# V1.net
KiCad netlist of a schematic drawn in EasyEDA Pro
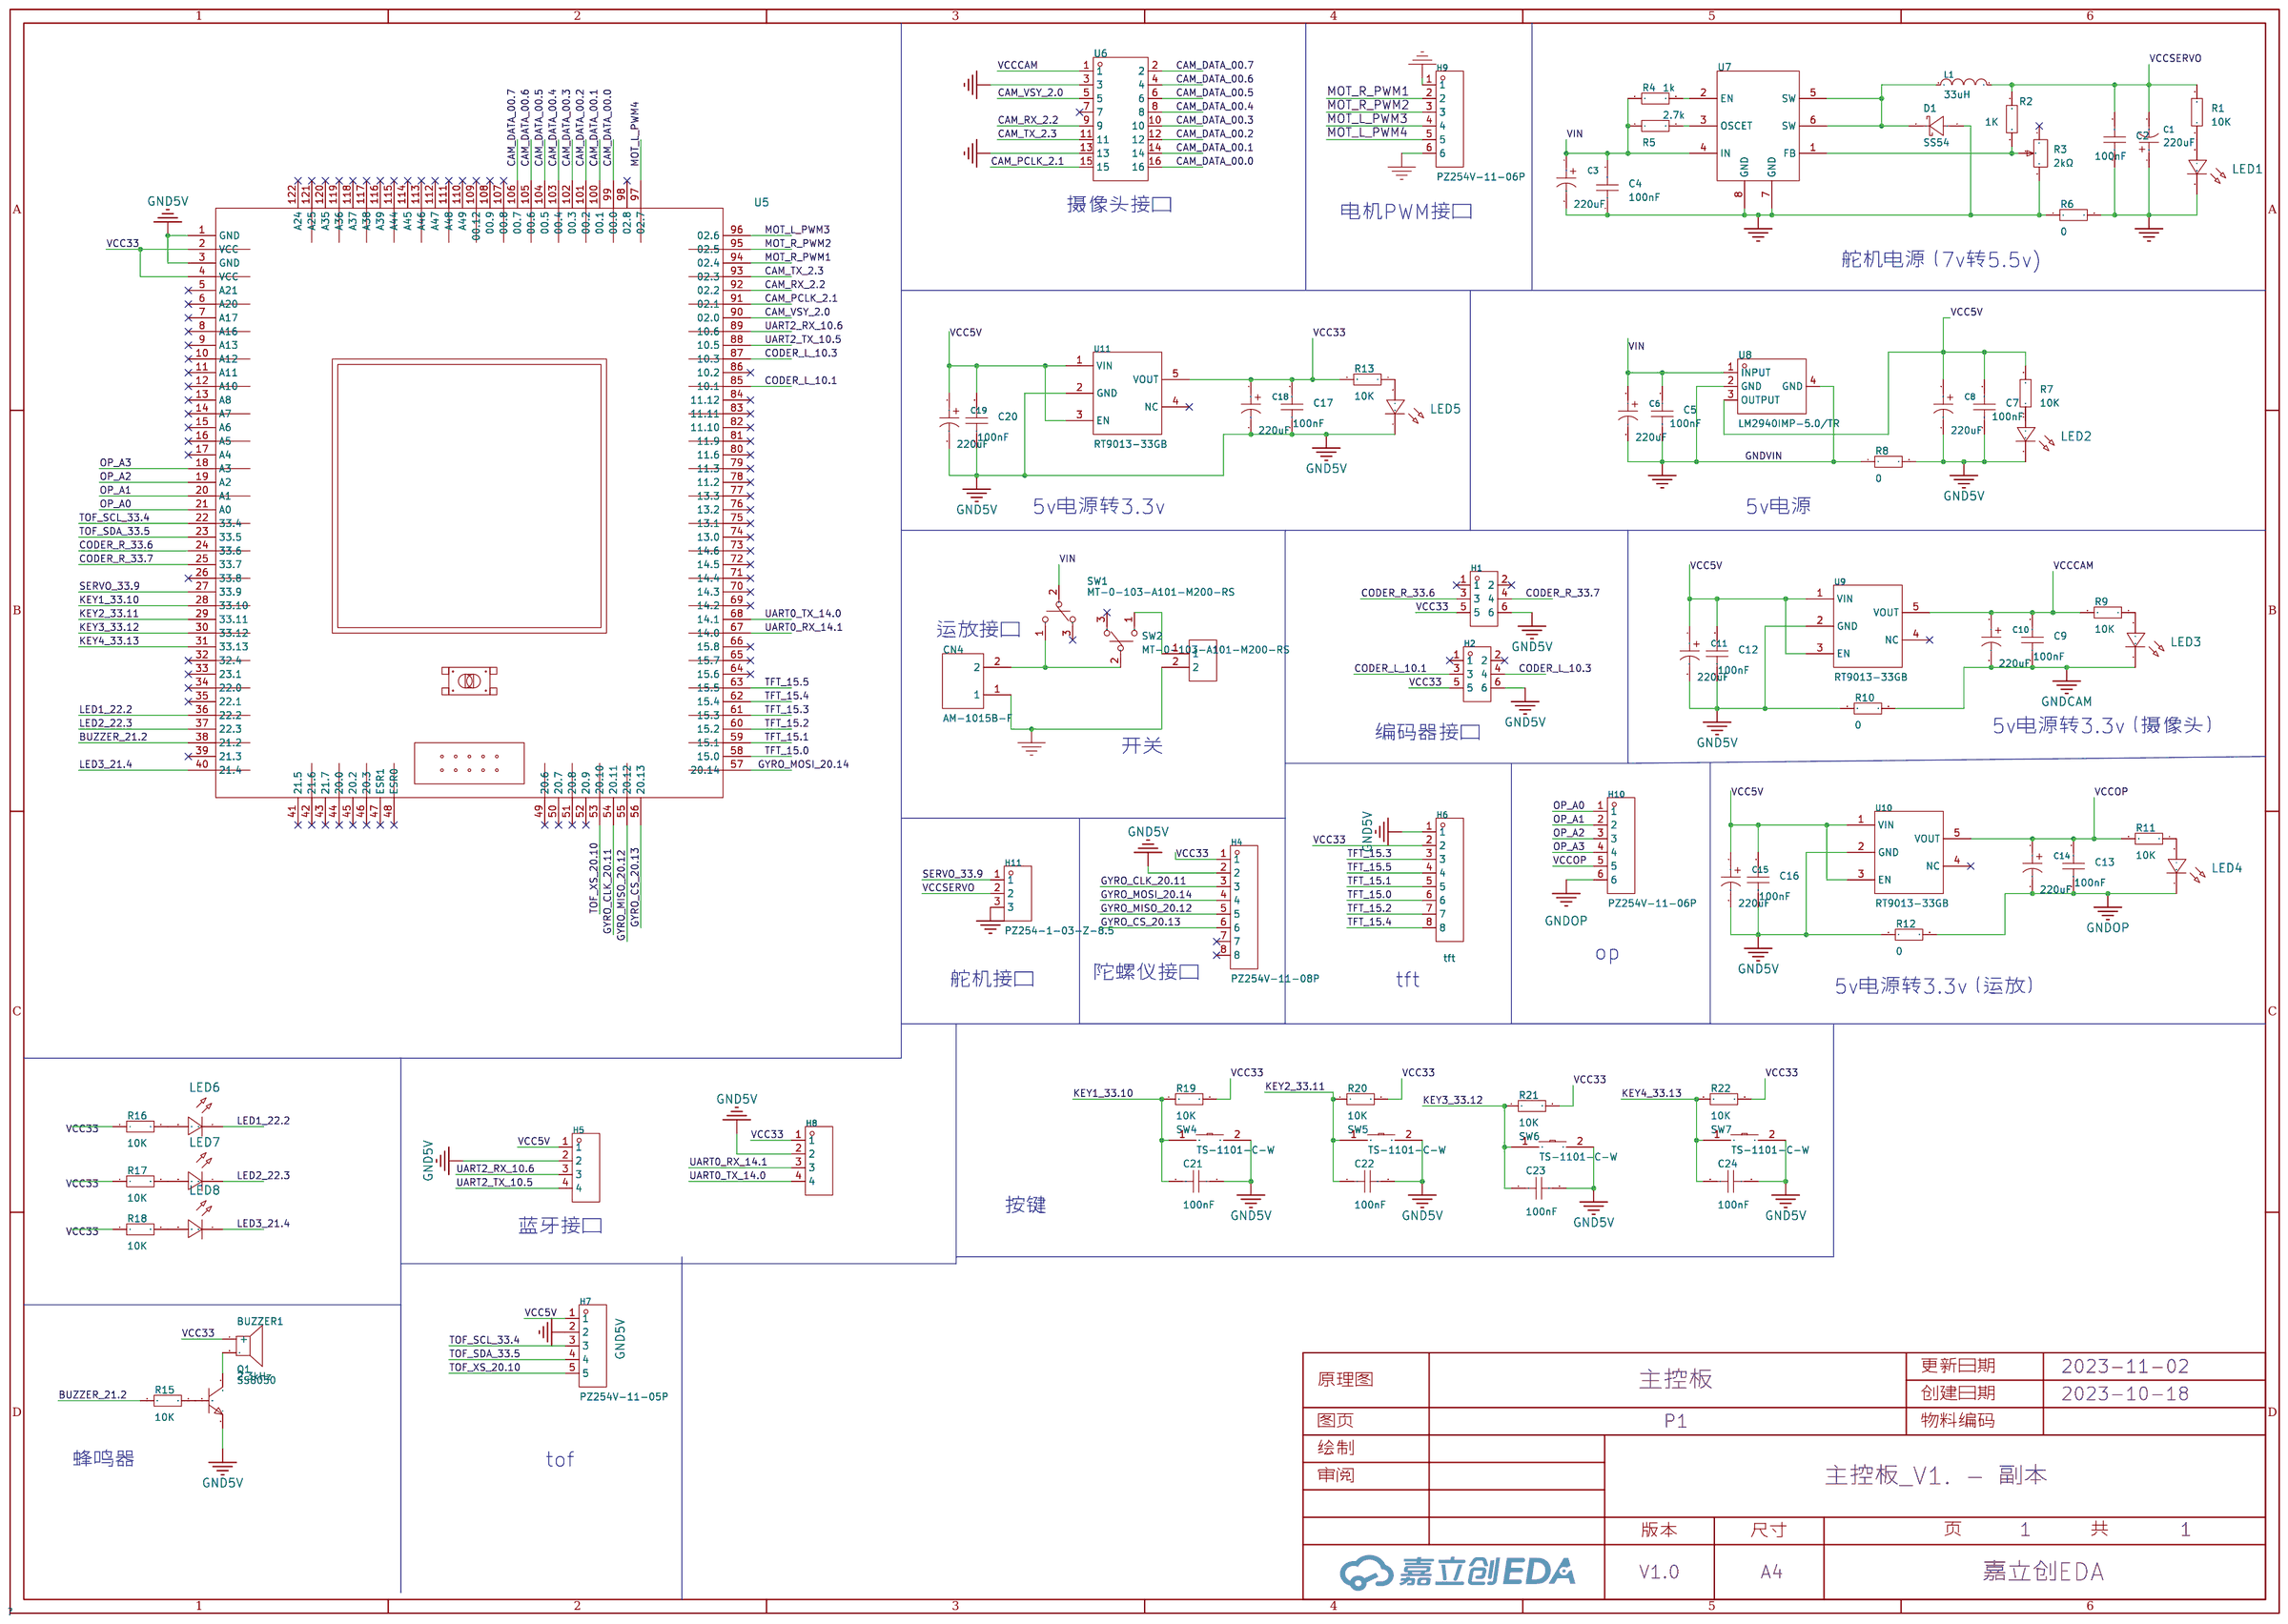
[diagram p0: schematic sheet]

(export (version "E")
  (design (tool "Eeschema 10.0.6"))
  (components
    (comp (ref "BUZZER1")
      (value "2.3kHz")
      (footprint "easyedapro:BUZ-TH_BD12.0-P7.60-D0.6-FD")
      (description "驱动方式:有源(内含驱动线路);构造类型:电磁式;额定电压:5V;频率:2.3kHz;声压(SPL):85dB@5V,10cm;")
      (fields (field (name "Manufacturer Part") "TMB12A05") (field (name "Manufacturer") "华能"))
      (libsource (lib "easyedapro") (part "TMB12A05"))
    )
    (comp (ref "C1")
      (value "220uF")
      (footprint "easyedapro:CAP-SMD_BD6.3-L6.6-W6.6-FD")
      (description "容值:220uF;精度:±20%;额定电压:16V;纹波电流:110mA@120Hz;等效串联电阻:-;")
      (fields
        (field (name "Manufacturer Part") "RVT220UF16V67RV0015")
        (field (name "Manufacturer") "KNSCHA(科尼盛)")
      )
      (libsource (lib "easyedapro") (part "RVT220UF16V67RV0015"))
    )
    (comp (ref "C2")
      (value "100nF")
      (footprint "easyedapro:C0603")
      (libsource (lib "easyedapro") (part "CapAcitance"))
    )
    (comp (ref "C3")
      (value "220uF")
      (footprint "easyedapro:CAP-SMD_BD6.3-L6.6-W6.6-FD")
      (description "容值:220uF;精度:±20%;额定电压:16V;纹波电流:110mA@120Hz;等效串联电阻:-;")
      (fields
        (field (name "Manufacturer Part") "RVT220UF16V67RV0015")
        (field (name "Manufacturer") "KNSCHA(科尼盛)")
      )
      (libsource (lib "easyedapro") (part "RVT220UF16V67RV0015"))
    )
    (comp (ref "C4")
      (value "100nF")
      (footprint "easyedapro:C0603")
      (libsource (lib "easyedapro") (part "CapAcitance"))
    )
    (comp (ref "C5")
      (value "100nF")
      (footprint "easyedapro:C0603")
      (libsource (lib "easyedapro") (part "CapAcitance"))
    )
    (comp (ref "C6")
      (value "220uF")
      (footprint "easyedapro:CAP-SMD_BD6.3-L6.6-W6.6-FD")
      (description "容值:220uF;精度:±20%;额定电压:16V;纹波电流:110mA@120Hz;等效串联电阻:-;")
      (fields
        (field (name "Manufacturer Part") "RVT220UF16V67RV0015")
        (field (name "Manufacturer") "KNSCHA(科尼盛)")
      )
      (libsource (lib "easyedapro") (part "RVT220UF16V67RV0015"))
    )
    (comp (ref "C7")
      (value "100nF")
      (footprint "easyedapro:C0603")
      (libsource (lib "easyedapro") (part "CapAcitance"))
    )
    (comp (ref "C8")
      (value "220uF")
      (footprint "easyedapro:CAP-SMD_BD6.3-L6.6-W6.6-FD")
      (description "容值:220uF;精度:±20%;额定电压:16V;纹波电流:110mA@120Hz;等效串联电阻:-;")
      (fields
        (field (name "Manufacturer Part") "RVT220UF16V67RV0015")
        (field (name "Manufacturer") "KNSCHA(科尼盛)")
      )
      (libsource (lib "easyedapro") (part "RVT220UF16V67RV0015"))
    )
    (comp (ref "C9")
      (value "100nF")
      (footprint "easyedapro:C0603")
      (libsource (lib "easyedapro") (part "CapAcitance"))
    )
    (comp (ref "C10")
      (value "220uF")
      (footprint "easyedapro:CAP-SMD_BD6.3-L6.6-W6.6-FD")
      (description "容值:220uF;精度:±20%;额定电压:16V;纹波电流:110mA@120Hz;等效串联电阻:-;")
      (fields
        (field (name "Manufacturer Part") "RVT220UF16V67RV0015")
        (field (name "Manufacturer") "KNSCHA(科尼盛)")
      )
      (libsource (lib "easyedapro") (part "RVT220UF16V67RV0015"))
    )
    (comp (ref "C11")
      (value "220uF")
      (footprint "easyedapro:CAP-SMD_BD6.3-L6.6-W6.6-FD")
      (description "容值:220uF;精度:±20%;额定电压:16V;纹波电流:110mA@120Hz;等效串联电阻:-;")
      (fields
        (field (name "Manufacturer Part") "RVT220UF16V67RV0015")
        (field (name "Manufacturer") "KNSCHA(科尼盛)")
      )
      (libsource (lib "easyedapro") (part "RVT220UF16V67RV0015"))
    )
    (comp (ref "C12")
      (value "100nF")
      (footprint "easyedapro:C0603")
      (libsource (lib "easyedapro") (part "CapAcitance"))
    )
    (comp (ref "C13")
      (value "100nF")
      (footprint "easyedapro:C0603")
      (libsource (lib "easyedapro") (part "CapAcitance"))
    )
    (comp (ref "C14")
      (value "220uF")
      (footprint "easyedapro:CAP-SMD_BD6.3-L6.6-W6.6-FD")
      (description "容值:220uF;精度:±20%;额定电压:16V;纹波电流:110mA@120Hz;等效串联电阻:-;")
      (fields
        (field (name "Manufacturer Part") "RVT220UF16V67RV0015")
        (field (name "Manufacturer") "KNSCHA(科尼盛)")
      )
      (libsource (lib "easyedapro") (part "RVT220UF16V67RV0015"))
    )
    (comp (ref "C15")
      (value "220uF")
      (footprint "easyedapro:CAP-SMD_BD6.3-L6.6-W6.6-FD")
      (description "容值:220uF;精度:±20%;额定电压:16V;纹波电流:110mA@120Hz;等效串联电阻:-;")
      (fields
        (field (name "Manufacturer Part") "RVT220UF16V67RV0015")
        (field (name "Manufacturer") "KNSCHA(科尼盛)")
      )
      (libsource (lib "easyedapro") (part "RVT220UF16V67RV0015"))
    )
    (comp (ref "C16")
      (value "100nF")
      (footprint "easyedapro:C0603")
      (libsource (lib "easyedapro") (part "CapAcitance"))
    )
    (comp (ref "C17")
      (value "100nF")
      (footprint "easyedapro:C0603")
      (libsource (lib "easyedapro") (part "CapAcitance"))
    )
    (comp (ref "C18")
      (value "220uF")
      (footprint "easyedapro:CAP-SMD_BD6.3-L6.6-W6.6-FD")
      (description "容值:220uF;精度:±20%;额定电压:16V;纹波电流:110mA@120Hz;等效串联电阻:-;")
      (fields
        (field (name "Manufacturer Part") "RVT220UF16V67RV0015")
        (field (name "Manufacturer") "KNSCHA(科尼盛)")
      )
      (libsource (lib "easyedapro") (part "RVT220UF16V67RV0015"))
    )
    (comp (ref "C19")
      (value "220uF")
      (footprint "easyedapro:CAP-SMD_BD6.3-L6.6-W6.6-FD")
      (description "容值:220uF;精度:±20%;额定电压:16V;纹波电流:110mA@120Hz;等效串联电阻:-;")
      (fields
        (field (name "Manufacturer Part") "RVT220UF16V67RV0015")
        (field (name "Manufacturer") "KNSCHA(科尼盛)")
      )
      (libsource (lib "easyedapro") (part "RVT220UF16V67RV0015"))
    )
    (comp (ref "C20")
      (value "100nF")
      (footprint "easyedapro:C0603")
      (libsource (lib "easyedapro") (part "CapAcitance"))
    )
    (comp (ref "C21")
      (value "100nF")
      (footprint "easyedapro:C0603")
      (libsource (lib "easyedapro") (part "CapAcitance"))
    )
    (comp (ref "C22")
      (value "100nF")
      (footprint "easyedapro:C0603")
      (libsource (lib "easyedapro") (part "CapAcitance"))
    )
    (comp (ref "C23")
      (value "100nF")
      (footprint "easyedapro:C0603")
      (libsource (lib "easyedapro") (part "CapAcitance"))
    )
    (comp (ref "C24")
      (value "100nF")
      (footprint "easyedapro:C0603")
      (libsource (lib "easyedapro") (part "CapAcitance"))
    )
    (comp (ref "CN4")
      (value "AM-1015B-F")
      (footprint "easyedapro:CONN-TH_AM-1015B-F")
      (description "金属材质：铜镀金  绝缘材质：PA")
      (fields (field (name "Manufacturer") "AMASS(艾迈斯)"))
      (libsource (lib "easyedapro") (part "AM-1015B-F"))
    )
    (comp (ref "D1")
      (value "SS54")
      (footprint "easyedapro:SMA_L4.3-W2.6-LS5.0-FD")
      (description "二极管配置:独立式;直流反向耐压(Vr):40V;平均整流电流(Io):5A;正向压降(Vf):550mV@5.0A;")
      (fields (field (name "Manufacturer") "宏迦橙"))
      (libsource (lib "easyedapro") (part "SS54_C7420369"))
    )
    (comp (ref "H1")
      (value "PZ254V-12-6P")
      (footprint "easyedapro:HDR-TH_6P-P2.54-V-M-R2-C3-S2.54")
      (fields (field (name "Manufacturer") "XFCN(兴飞)"))
      (libsource (lib "easyedapro") (part "PZ254V-12-6P"))
    )
    (comp (ref "H2")
      (value "PZ254V-12-6P")
      (footprint "easyedapro:HDR-TH_6P-P2.54-V-M-R2-C3-S2.54")
      (fields (field (name "Manufacturer") "XFCN(兴飞)"))
      (libsource (lib "easyedapro") (part "PZ254V-12-6P"))
    )
    (comp (ref "H4")
      (value "PZ254V-11-08P")
      (footprint "easyedapro:HDR-TH_8P-P2.54-V-M")
      (fields (field (name "Manufacturer") "XFCN(兴飞)"))
      (libsource (lib "easyedapro") (part "PZ254V-11-08P"))
    )
    (comp (ref "H5")
      (value "PZ254V-11-04P")
      (footprint "easyedapro:HDR-TH_4P-P2.54-V-M")
      (fields (field (name "Manufacturer") "XFCN(兴飞)"))
      (libsource (lib "easyedapro") (part "PZ254V-11-04P_C2691448"))
    )
    (comp (ref "H6")
      (value "tft")
      (footprint "easyedapro:HDR-TH_8P-P2.54-V-M")
      (fields (field (name "Manufacturer") "XFCN(兴飞)"))
      (libsource (lib "easyedapro") (part "PZ254V-11-08P"))
    )
    (comp (ref "H7")
      (value "PZ254V-11-05P")
      (footprint "easyedapro:HDR-TH_5P-P2.54-V-M")
      (fields (field (name "Manufacturer") "XFCN(兴飞)"))
      (libsource (lib "easyedapro") (part "PZ254V-11-05P"))
    )
    (comp (ref "H8")
      (value "PZ254V-11-04P")
      (footprint "easyedapro:HDR-TH_4P-P2.54-V-M")
      (fields (field (name "Manufacturer") "XFCN(兴飞)"))
      (libsource (lib "easyedapro") (part "PZ254V-11-04P_C2691448"))
    )
    (comp (ref "H9")
      (value "PZ254V-11-06P")
      (footprint "easyedapro:HDR-TH_6P-P2.54-V-M")
      (fields (field (name "Manufacturer") "XFCN(兴飞)"))
      (libsource (lib "easyedapro") (part "PZ254V-11-06P"))
    )
    (comp (ref "H10")
      (value "PZ254V-11-06P")
      (footprint "easyedapro:HDR-TH_6P-P2.54-V-M")
      (fields (field (name "Manufacturer") "XFCN(兴飞)"))
      (libsource (lib "easyedapro") (part "PZ254V-11-06P"))
    )
    (comp (ref "H11")
      (value "PZ254-1-03-Z-8.5")
      (footprint "easyedapro:HDR-TH_03P-P2.54-V-M")
      (fields (field (name "Manufacturer") "HCTL(华灿天禄)"))
      (libsource (lib "easyedapro") (part "PZ254-1-03-Z-8.5"))
    )
    (comp (ref "L1")
      (value "33uH")
      (footprint "easyedapro:IND-SMD_L7.0-W6.6_FXL0630")
      (description "类型:一体成型电感;电感值:33uH;精度:±20%;额定电流:2A;饱和电流(Isat):2.5A;")
      (fields (field (name "Manufacturer Part") "FXL0630-330-M") (field (name "Manufacturer") "cjiang(长江微电)"))
      (libsource (lib "easyedapro") (part "FXL0630-330-M"))
    )
    (comp (ref "LED1")
      (value "~")
      (footprint "easyedapro:LED_0603")
      (libsource (lib "easyedapro") (part "LED_R"))
    )
    (comp (ref "LED2")
      (value "~")
      (footprint "easyedapro:LED_0603")
      (libsource (lib "easyedapro") (part "LED_R"))
    )
    (comp (ref "LED3")
      (value "~")
      (footprint "easyedapro:LED_0603")
      (libsource (lib "easyedapro") (part "LED_R"))
    )
    (comp (ref "LED4")
      (value "~")
      (footprint "easyedapro:LED_0603")
      (libsource (lib "easyedapro") (part "LED_R"))
    )
    (comp (ref "LED5")
      (value "~")
      (footprint "easyedapro:LED_0603")
      (libsource (lib "easyedapro") (part "LED_R"))
    )
    (comp (ref "LED6")
      (value "~")
      (footprint "easyedapro:LED_0603")
      (libsource (lib "easyedapro") (part "LED_R"))
    )
    (comp (ref "LED7")
      (value "~")
      (footprint "easyedapro:LED_0603")
      (libsource (lib "easyedapro") (part "LED_R"))
    )
    (comp (ref "LED8")
      (value "~")
      (footprint "easyedapro:LED_0603")
      (libsource (lib "easyedapro") (part "LED_R"))
    )
    (comp (ref "P1")
      (value "WJ500V-5.08-2P")
      (footprint "easyedapro:CONN-TH_2P-P5.00_WJ500V-5.08-2P")
      (fields (field (name "Manufacturer") "KANGNEX(康奈克斯电气)"))
      (libsource (lib "easyedapro") (part "WJ500V-5.08-2P-14-00A"))
    )
    (comp (ref "Q1")
      (value "SS8050")
      (footprint "easyedapro:SOT-23-3_L2.9-W1.3-P1.90-LS2.4-BR")
      (description "晶体管类型:NPN;集射极击穿电压(Vceo):25V;集电极电流(Ic):1.5A;功率(Pd):300mW;直流电流增益(hFE@Ic,Vce):200@100mA,1V;")
      (fields (field (name "Manufacturer") "CJ(江苏长电/长晶)"))
      (libsource (lib "easyedapro") (part "SS8050_C2150"))
    )
    (comp (ref "R1") (value "10K") (footprint "easyedapro:R0603") (libsource (lib "easyedapro") (part "电阻")))
    (comp (ref "R2") (value "1K") (footprint "easyedapro:R0603") (libsource (lib "easyedapro") (part "电阻")))
    (comp (ref "R3")
      (value "2kΩ")
      (footprint "easyedapro:RES-ADJ-TH_3296W")
      (description "阻值:1kΩ;精度:±10%;功率:500mW;")
      (fields (field (name "Manufacturer Part") "3296W-1-102LF") (field (name "Manufacturer") "BOURNS"))
      (libsource (lib "easyedapro") (part "3296W-1-102LF"))
    )
    (comp (ref "R4") (value "1k") (footprint "easyedapro:R0603") (libsource (lib "easyedapro") (part "电阻")))
    (comp (ref "R5") (value "2.7k") (footprint "easyedapro:R0603") (libsource (lib "easyedapro") (part "电阻")))
    (comp (ref "R6") (value "0") (footprint "easyedapro:R0603") (libsource (lib "easyedapro") (part "电阻")))
    (comp (ref "R7") (value "10K") (footprint "easyedapro:R0603") (libsource (lib "easyedapro") (part "电阻")))
    (comp (ref "R8") (value "0") (footprint "easyedapro:R0603") (libsource (lib "easyedapro") (part "电阻")))
    (comp (ref "R9") (value "10K") (footprint "easyedapro:R0603") (libsource (lib "easyedapro") (part "电阻")))
    (comp (ref "R10") (value "0") (footprint "easyedapro:R0603") (libsource (lib "easyedapro") (part "电阻")))
    (comp (ref "R11") (value "10K") (footprint "easyedapro:R0603") (libsource (lib "easyedapro") (part "电阻")))
    (comp (ref "R12") (value "0") (footprint "easyedapro:R0603") (libsource (lib "easyedapro") (part "电阻")))
    (comp (ref "R13") (value "10K") (footprint "easyedapro:R0603") (libsource (lib "easyedapro") (part "电阻")))
    (comp (ref "R15") (value "10K") (footprint "easyedapro:R0603") (libsource (lib "easyedapro") (part "电阻")))
    (comp (ref "R16") (value "10K") (footprint "easyedapro:R0603") (libsource (lib "easyedapro") (part "电阻")))
    (comp (ref "R17") (value "10K") (footprint "easyedapro:R0603") (libsource (lib "easyedapro") (part "电阻")))
    (comp (ref "R18") (value "10K") (footprint "easyedapro:R0603") (libsource (lib "easyedapro") (part "电阻")))
    (comp (ref "R19") (value "10K") (footprint "easyedapro:R0603") (libsource (lib "easyedapro") (part "电阻")))
    (comp (ref "R20") (value "10K") (footprint "easyedapro:R0603") (libsource (lib "easyedapro") (part "电阻")))
    (comp (ref "R21") (value "10K") (footprint "easyedapro:R0603") (libsource (lib "easyedapro") (part "电阻")))
    (comp (ref "R22") (value "10K") (footprint "easyedapro:R0603") (libsource (lib "easyedapro") (part "电阻")))
    (comp (ref "SW1")
      (value "MT-0-103-A101-M200-RS")
      (footprint "easyedapro:SW-TH_MT-0-103-A101-M200-RS")
      (description "额定电流:5A;额定电压(AC):125V;电路结构:单刀双掷;机械寿命:-;安装方式:直插;")
      (fields (field (name "Manufacturer") "YUEN FUNG(源丰)"))
      (libsource (lib "easyedapro") (part "MT-0-103-A101-M200-RS+PJ"))
    )
    (comp (ref "SW2")
      (value "MT-0-103-A101-M200-RS")
      (footprint "easyedapro:SW-TH_MT-0-103-A101-M200-RS")
      (description "额定电流:5A;额定电压(AC):125V;电路结构:单刀双掷;机械寿命:-;安装方式:直插;")
      (fields (field (name "Manufacturer") "YUEN FUNG(源丰)"))
      (libsource (lib "easyedapro") (part "MT-0-103-A101-M200-RS+PJ"))
    )
    (comp (ref "SW4")
      (value "TS-1101-C-W")
      (footprint "easyedapro:SW-SMD_L6.0-W3.3-LS8.0")
      (description "触点电流:50mA;额定电压(AC):-;额定电压(DC):12V;额定功率:-;绝缘电阻:-;电路结构:单刀单掷;安装方式:立贴;带灯:无;作用力:260gf;机械寿命:5万次;带支架:否;")
      (fields (field (name "Manufacturer") "XKB Connectivity(中国星坤)"))
      (libsource (lib "easyedapro") (part "TS-1101-C-W"))
    )
    (comp (ref "SW5")
      (value "TS-1101-C-W")
      (footprint "easyedapro:SW-SMD_L6.0-W3.3-LS8.0")
      (description "触点电流:50mA;额定电压(AC):-;额定电压(DC):12V;额定功率:-;绝缘电阻:-;电路结构:单刀单掷;安装方式:立贴;带灯:无;作用力:260gf;机械寿命:5万次;带支架:否;")
      (fields (field (name "Manufacturer") "XKB Connectivity(中国星坤)"))
      (libsource (lib "easyedapro") (part "TS-1101-C-W"))
    )
    (comp (ref "SW6")
      (value "TS-1101-C-W")
      (footprint "easyedapro:SW-SMD_L6.0-W3.3-LS8.0")
      (description "触点电流:50mA;额定电压(AC):-;额定电压(DC):12V;额定功率:-;绝缘电阻:-;电路结构:单刀单掷;安装方式:立贴;带灯:无;作用力:260gf;机械寿命:5万次;带支架:否;")
      (fields (field (name "Manufacturer") "XKB Connectivity(中国星坤)"))
      (libsource (lib "easyedapro") (part "TS-1101-C-W"))
    )
    (comp (ref "SW7")
      (value "TS-1101-C-W")
      (footprint "easyedapro:SW-SMD_L6.0-W3.3-LS8.0")
      (description "触点电流:50mA;额定电压(AC):-;额定电压(DC):12V;额定功率:-;绝缘电阻:-;电路结构:单刀单掷;安装方式:立贴;带灯:无;作用力:260gf;机械寿命:5万次;带支架:否;")
      (fields (field (name "Manufacturer") "XKB Connectivity(中国星坤)"))
      (libsource (lib "easyedapro") (part "TS-1101-C-W"))
    )
    (comp (ref "U5")
      (value "TC264_CoreBoard")
      (description "TC264核心板")
      (libsource (lib "easyedapro") (part "TC264"))
    )
    (comp (ref "U6")
      (value "PM254-2-08-Z-8.5")
      (footprint "easyedapro:HDR-TH_16P-P2.54-V-F-R2-C8-S2.54")
      (fields (field (name "Manufacturer") "HCTL(华灿天禄)"))
      (libsource (lib "easyedapro") (part "PM254-2-08-Z-8.5"))
    )
    (comp (ref "U7") (value "~") (libsource (lib "easyedapro") (part "aaa")))
    (comp (ref "U8")
      (value "LM2940IMP-5.0/TR")
      (footprint "easyedapro:SOT-223-3_L6.5-W3.4-P2.30-LS7.0-BR")
      (description "输出类型:-;")
      (fields (field (name "Manufacturer") "HGSEMI(华冠)"))
      (libsource (lib "easyedapro") (part "LM2940IMP-5.0/TR"))
    )
    (comp (ref "U9")
      (value "RT9013-33GB")
      (footprint "easyedapro:SOT-23-5_L3.0-W1.7-P0.95-LS2.8-BL")
      (description "输出类型:固定;输出极性:正;最大输入电压:5.5V;输出电压:3.3V;输出电流:500mA;电源纹波抑制比(PSRR):50dB@(10kHz);")
      (fields (field (name "Manufacturer") "RICHTEK(立锜)"))
      (libsource (lib "easyedapro") (part "RT9013-33GB"))
    )
    (comp (ref "U10")
      (value "RT9013-33GB")
      (footprint "easyedapro:SOT-23-5_L3.0-W1.7-P0.95-LS2.8-BL")
      (description "输出类型:固定;输出极性:正;最大输入电压:5.5V;输出电压:3.3V;输出电流:500mA;电源纹波抑制比(PSRR):50dB@(10kHz);")
      (fields (field (name "Manufacturer") "RICHTEK(立锜)"))
      (libsource (lib "easyedapro") (part "RT9013-33GB"))
    )
    (comp (ref "U11")
      (value "RT9013-33GB")
      (footprint "easyedapro:SOT-23-5_L3.0-W1.7-P0.95-LS2.8-BL")
      (description "输出类型:固定;输出极性:正;最大输入电压:5.5V;输出电压:3.3V;输出电流:500mA;电源纹波抑制比(PSRR):50dB@(10kHz);")
      (fields (field (name "Manufacturer") "RICHTEK(立锜)"))
      (libsource (lib "easyedapro") (part "RT9013-33GB"))
    )
  )
  (nets
    (net (code "1") (name "/BUZZER_21.2") (class "Default")
      (node (ref "R15") (pin "2") (pinfunction "2_2") (pintype "input"))
      (node (ref "U5") (pin "38") (pinfunction "21.2_38") (pintype "input"))
    )
    (net (code "2") (name "/CAM_DATA_00.0") (class "Default")
      (node (ref "U5") (pin "99") (pinfunction "00.0_99") (pintype "input"))
      (node (ref "U6") (pin "16") (pinfunction "16_16") (pintype "unspecified"))
    )
    (net (code "3") (name "/CAM_DATA_00.1") (class "Default")
      (node (ref "U5") (pin "100") (pinfunction "00.1_100") (pintype "input"))
      (node (ref "U6") (pin "14") (pinfunction "14_14") (pintype "unspecified"))
    )
    (net (code "4") (name "/CAM_DATA_00.2") (class "Default")
      (node (ref "U5") (pin "101") (pinfunction "00.2_101") (pintype "input"))
      (node (ref "U6") (pin "12") (pinfunction "12_12") (pintype "unspecified"))
    )
    (net (code "5") (name "/CAM_DATA_00.3") (class "Default")
      (node (ref "U5") (pin "102") (pinfunction "00.3_102") (pintype "input"))
      (node (ref "U6") (pin "10") (pinfunction "10_10") (pintype "unspecified"))
    )
    (net (code "6") (name "/CAM_DATA_00.4") (class "Default")
      (node (ref "U5") (pin "103") (pinfunction "00.4_103") (pintype "input"))
      (node (ref "U6") (pin "8") (pinfunction "8_8") (pintype "unspecified"))
    )
    (net (code "7") (name "/CAM_DATA_00.5") (class "Default")
      (node (ref "U5") (pin "104") (pinfunction "00.5_104") (pintype "input"))
      (node (ref "U6") (pin "6") (pinfunction "6_6") (pintype "unspecified"))
    )
    (net (code "8") (name "/CAM_DATA_00.6") (class "Default")
      (node (ref "U5") (pin "105") (pinfunction "00.6_105") (pintype "input"))
      (node (ref "U6") (pin "4") (pinfunction "4_4") (pintype "unspecified"))
    )
    (net (code "9") (name "/CAM_DATA_00.7") (class "Default")
      (node (ref "U5") (pin "106") (pinfunction "00.7_106") (pintype "input"))
      (node (ref "U6") (pin "2") (pinfunction "2_2") (pintype "unspecified"))
    )
    (net (code "10") (name "/CAM_PCLK_2.1") (class "Default")
      (node (ref "U5") (pin "91") (pinfunction "02.1_91") (pintype "input"))
      (node (ref "U6") (pin "15") (pinfunction "15_15") (pintype "unspecified"))
    )
    (net (code "11") (name "/CAM_RX_2.2") (class "Default")
      (node (ref "U5") (pin "92") (pinfunction "02.2_92") (pintype "input"))
      (node (ref "U6") (pin "9") (pinfunction "9_9") (pintype "unspecified"))
    )
    (net (code "12") (name "/CAM_TX_2.3") (class "Default")
      (node (ref "U5") (pin "93") (pinfunction "02.3_93") (pintype "input"))
      (node (ref "U6") (pin "11") (pinfunction "11_11") (pintype "unspecified"))
    )
    (net (code "13") (name "/CAM_VSY_2.0") (class "Default")
      (node (ref "U5") (pin "90") (pinfunction "02.0_90") (pintype "input"))
      (node (ref "U6") (pin "5") (pinfunction "5_5") (pintype "unspecified"))
    )
    (net (code "14") (name "/CODER_L_10.1") (class "Default")
      (node (ref "H2") (pin "3") (pinfunction "3_3") (pintype "input"))
      (node (ref "U5") (pin "85") (pinfunction "10.1_85") (pintype "input"))
    )
    (net (code "15") (name "/CODER_L_10.3") (class "Default")
      (node (ref "H2") (pin "4") (pinfunction "4_4") (pintype "input"))
      (node (ref "U5") (pin "87") (pinfunction "10.3_87") (pintype "input"))
    )
    (net (code "16") (name "/CODER_R_33.6") (class "Default")
      (node (ref "H1") (pin "3") (pinfunction "3_3") (pintype "input"))
      (node (ref "U5") (pin "24") (pinfunction "33.6_24") (pintype "input"))
    )
    (net (code "17") (name "/CODER_R_33.7") (class "Default")
      (node (ref "H1") (pin "4") (pinfunction "4_4") (pintype "input"))
      (node (ref "U5") (pin "25") (pinfunction "33.7_25") (pintype "input"))
    )
    (net (code "18") (name "/GYRO_CLK_20.11") (class "Default")
      (node (ref "H4") (pin "3") (pinfunction "3_3") (pintype "input"))
      (node (ref "U5") (pin "54") (pinfunction "20.11_54") (pintype "input"))
    )
    (net (code "19") (name "/GYRO_CS_20.13") (class "Default")
      (node (ref "H4") (pin "6") (pinfunction "6_6") (pintype "input"))
      (node (ref "U5") (pin "56") (pinfunction "20.13_56") (pintype "input"))
    )
    (net (code "20") (name "/GYRO_MISO_20.12") (class "Default")
      (node (ref "H4") (pin "5") (pinfunction "5_5") (pintype "input"))
      (node (ref "U5") (pin "55") (pinfunction "20.12_55") (pintype "input"))
    )
    (net (code "21") (name "/GYRO_MOSI_20.14") (class "Default")
      (node (ref "H4") (pin "4") (pinfunction "4_4") (pintype "input"))
      (node (ref "U5") (pin "57") (pinfunction "20.14_57") (pintype "input"))
    )
    (net (code "22") (name "/KEY1_33.10") (class "Default")
      (node (ref "C21") (pin "1") (pinfunction "1_1") (pintype "input"))
      (node (ref "R19") (pin "1") (pinfunction "1_1") (pintype "input"))
      (node (ref "SW4") (pin "1") (pinfunction "1_1") (pintype "input"))
      (node (ref "U5") (pin "28") (pinfunction "33.10_28") (pintype "input"))
    )
    (net (code "23") (name "/KEY2_33.11") (class "Default")
      (node (ref "C22") (pin "1") (pinfunction "1_1") (pintype "input"))
      (node (ref "R20") (pin "1") (pinfunction "1_1") (pintype "input"))
      (node (ref "SW5") (pin "1") (pinfunction "1_1") (pintype "input"))
      (node (ref "U5") (pin "29") (pinfunction "33.11_29") (pintype "input"))
    )
    (net (code "24") (name "/KEY3_33.12") (class "Default")
      (node (ref "C23") (pin "1") (pinfunction "1_1") (pintype "input"))
      (node (ref "R21") (pin "1") (pinfunction "1_1") (pintype "input"))
      (node (ref "SW6") (pin "1") (pinfunction "1_1") (pintype "input"))
      (node (ref "U5") (pin "30") (pinfunction "33.12_30") (pintype "input"))
    )
    (net (code "25") (name "/KEY4_33.13") (class "Default")
      (node (ref "C24") (pin "1") (pinfunction "1_1") (pintype "input"))
      (node (ref "R22") (pin "1") (pinfunction "1_1") (pintype "input"))
      (node (ref "SW7") (pin "1") (pinfunction "1_1") (pintype "input"))
      (node (ref "U5") (pin "31") (pinfunction "33.13_31") (pintype "input"))
    )
    (net (code "26") (name "/LED1_22.2") (class "Default")
      (node (ref "LED6") (pin "1") (pinfunction "C_1") (pintype "input"))
      (node (ref "U5") (pin "36") (pinfunction "22.2_36") (pintype "input"))
    )
    (net (code "27") (name "/LED2_22.3") (class "Default")
      (node (ref "LED7") (pin "1") (pinfunction "C_1") (pintype "input"))
      (node (ref "U5") (pin "37") (pinfunction "22.3_37") (pintype "input"))
    )
    (net (code "28") (name "/LED3_21.4") (class "Default")
      (node (ref "LED8") (pin "1") (pinfunction "C_1") (pintype "input"))
      (node (ref "U5") (pin "40") (pinfunction "21.4_40") (pintype "input"))
    )
    (net (code "29") (name "/MOT_L_PWM3") (class "Default")
      (node (ref "H9") (pin "4") (pinfunction "4_4") (pintype "input"))
      (node (ref "U5") (pin "96") (pinfunction "02.6_96") (pintype "input"))
    )
    (net (code "30") (name "/MOT_L_PWM4") (class "Default")
      (node (ref "H9") (pin "5") (pinfunction "5_5") (pintype "input"))
      (node (ref "U5") (pin "97") (pinfunction "02.7_97") (pintype "input"))
    )
    (net (code "31") (name "/MOT_R_PWM1") (class "Default")
      (node (ref "H9") (pin "2") (pinfunction "2_2") (pintype "input"))
      (node (ref "U5") (pin "94") (pinfunction "02.4_94") (pintype "input"))
    )
    (net (code "32") (name "/MOT_R_PWM2") (class "Default")
      (node (ref "H9") (pin "3") (pinfunction "3_3") (pintype "input"))
      (node (ref "U5") (pin "95") (pinfunction "02.5_95") (pintype "input"))
    )
    (net (code "33") (name "/OP_A0") (class "Default")
      (node (ref "H10") (pin "1") (pinfunction "1_1") (pintype "input"))
      (node (ref "U5") (pin "21") (pinfunction "A0_21") (pintype "input"))
    )
    (net (code "34") (name "/OP_A1") (class "Default")
      (node (ref "H10") (pin "2") (pinfunction "2_2") (pintype "input"))
      (node (ref "U5") (pin "20") (pinfunction "A1_20") (pintype "input"))
    )
    (net (code "35") (name "/OP_A2") (class "Default")
      (node (ref "H10") (pin "3") (pinfunction "3_3") (pintype "input"))
      (node (ref "U5") (pin "19") (pinfunction "A2_19") (pintype "input"))
    )
    (net (code "36") (name "/OP_A3") (class "Default")
      (node (ref "H10") (pin "4") (pinfunction "4_4") (pintype "input"))
      (node (ref "U5") (pin "18") (pinfunction "A3_18") (pintype "input"))
    )
    (net (code "37") (name "/SERVO_33.9") (class "Default")
      (node (ref "H11") (pin "1") (pinfunction "1_1") (pintype "input"))
      (node (ref "U5") (pin "27") (pinfunction "33.9_27") (pintype "input"))
    )
    (net (code "38") (name "/TFT_15.0") (class "Default")
      (node (ref "H6") (pin "6") (pinfunction "6_6") (pintype "input"))
      (node (ref "U5") (pin "58") (pinfunction "15.0_58") (pintype "input"))
    )
    (net (code "39") (name "/TFT_15.1") (class "Default")
      (node (ref "H6") (pin "5") (pinfunction "5_5") (pintype "input"))
      (node (ref "U5") (pin "59") (pinfunction "15.1_59") (pintype "input"))
    )
    (net (code "40") (name "/TFT_15.2") (class "Default")
      (node (ref "H6") (pin "7") (pinfunction "7_7") (pintype "input"))
      (node (ref "U5") (pin "60") (pinfunction "15.2_60") (pintype "input"))
    )
    (net (code "41") (name "/TFT_15.3") (class "Default")
      (node (ref "H6") (pin "3") (pinfunction "3_3") (pintype "input"))
      (node (ref "U5") (pin "61") (pinfunction "15.3_61") (pintype "input"))
    )
    (net (code "42") (name "/TFT_15.4") (class "Default")
      (node (ref "H6") (pin "8") (pinfunction "8_8") (pintype "input"))
      (node (ref "U5") (pin "62") (pinfunction "15.4_62") (pintype "input"))
    )
    (net (code "43") (name "/TFT_15.5") (class "Default")
      (node (ref "H6") (pin "4") (pinfunction "4_4") (pintype "input"))
      (node (ref "U5") (pin "63") (pinfunction "15.5_63") (pintype "input"))
    )
    (net (code "44") (name "/TOF_SCL_33.4") (class "Default")
      (node (ref "H7") (pin "3") (pinfunction "3_3") (pintype "input"))
      (node (ref "U5") (pin "22") (pinfunction "33.4_22") (pintype "input"))
    )
    (net (code "45") (name "/TOF_SDA_33.5") (class "Default")
      (node (ref "H7") (pin "4") (pinfunction "4_4") (pintype "input"))
      (node (ref "U5") (pin "23") (pinfunction "33.5_23") (pintype "input"))
    )
    (net (code "46") (name "/TOF_XS_20.10") (class "Default")
      (node (ref "H7") (pin "5") (pinfunction "5_5") (pintype "input"))
      (node (ref "U5") (pin "53") (pinfunction "20.10_53") (pintype "input"))
    )
    (net (code "47") (name "/UART0_RX_14.1") (class "Default")
      (node (ref "H8") (pin "3") (pinfunction "3_3") (pintype "input"))
      (node (ref "U5") (pin "67") (pinfunction "14.0_67") (pintype "input"))
    )
    (net (code "48") (name "/UART0_TX_14.0") (class "Default")
      (node (ref "H8") (pin "4") (pinfunction "4_4") (pintype "input"))
      (node (ref "U5") (pin "68") (pinfunction "14.1_68") (pintype "input"))
    )
    (net (code "49") (name "/UART2_RX_10.6") (class "Default")
      (node (ref "H5") (pin "3") (pinfunction "3_3") (pintype "input"))
      (node (ref "U5") (pin "89") (pinfunction "10.6_89") (pintype "input"))
    )
    (net (code "50") (name "/UART2_TX_10.5") (class "Default")
      (node (ref "H5") (pin "4") (pinfunction "4_4") (pintype "input"))
      (node (ref "U5") (pin "88") (pinfunction "10.5_88") (pintype "input"))
    )
    (net (code "51") (name "/VCC5V") (class "Default")
      (node (ref "C11") (pin "1") (pinfunction "1_1") (pintype "input"))
      (node (ref "C12") (pin "2") (pinfunction "2_2") (pintype "input"))
      (node (ref "C15") (pin "1") (pinfunction "1_1") (pintype "input"))
      (node (ref "C16") (pin "2") (pinfunction "2_2") (pintype "input"))
      (node (ref "C19") (pin "1") (pinfunction "1_1") (pintype "input"))
      (node (ref "C20") (pin "2") (pinfunction "2_2") (pintype "input"))
      (node (ref "C7") (pin "2") (pinfunction "2_2") (pintype "input"))
      (node (ref "C8") (pin "1") (pinfunction "1_1") (pintype "input"))
      (node (ref "H5") (pin "1") (pinfunction "1_1") (pintype "input"))
      (node (ref "H7") (pin "1") (pinfunction "1_1") (pintype "input"))
      (node (ref "R7") (pin "2") (pinfunction "2_2") (pintype "input"))
      (node (ref "U10") (pin "1") (pinfunction "VIN_1") (pintype "input"))
      (node (ref "U10") (pin "3") (pinfunction "EN_3") (pintype "input"))
      (node (ref "U11") (pin "1") (pinfunction "VIN_1") (pintype "input"))
      (node (ref "U11") (pin "3") (pinfunction "EN_3") (pintype "input"))
      (node (ref "U8") (pin "3") (pinfunction "OUTPUT_3") (pintype "input"))
      (node (ref "U9") (pin "1") (pinfunction "VIN_1") (pintype "input"))
      (node (ref "U9") (pin "3") (pinfunction "EN_3") (pintype "input"))
    )
    (net (code "52") (name "/VCC33") (class "Default")
      (node (ref "BUZZER1") (pin "1") (pinfunction "+_1") (pintype "input"))
      (node (ref "C17") (pin "2") (pinfunction "2_2") (pintype "input"))
      (node (ref "C18") (pin "1") (pinfunction "1_1") (pintype "input"))
      (node (ref "H1") (pin "5") (pinfunction "5_5") (pintype "input"))
      (node (ref "H2") (pin "5") (pinfunction "5_5") (pintype "input"))
      (node (ref "H4") (pin "1") (pinfunction "1_1") (pintype "input"))
      (node (ref "H6") (pin "2") (pinfunction "2_2") (pintype "input"))
      (node (ref "H8") (pin "1") (pinfunction "1_1") (pintype "input"))
      (node (ref "R13") (pin "2") (pinfunction "2_2") (pintype "input"))
      (node (ref "R16") (pin "1") (pinfunction "1_1") (pintype "input"))
      (node (ref "R17") (pin "1") (pinfunction "1_1") (pintype "input"))
      (node (ref "R18") (pin "1") (pinfunction "1_1") (pintype "input"))
      (node (ref "R19") (pin "2") (pinfunction "2_2") (pintype "input"))
      (node (ref "R20") (pin "2") (pinfunction "2_2") (pintype "input"))
      (node (ref "R21") (pin "2") (pinfunction "2_2") (pintype "input"))
      (node (ref "R22") (pin "2") (pinfunction "2_2") (pintype "input"))
      (node (ref "U11") (pin "5") (pinfunction "VOUT_5") (pintype "input"))
      (node (ref "U5") (pin "2") (pinfunction "VCC_2") (pintype "input"))
      (node (ref "U5") (pin "4") (pinfunction "VCC_4") (pintype "input"))
    )
    (net (code "53") (name "/VCCCAM") (class "Default")
      (node (ref "C10") (pin "1") (pinfunction "1_1") (pintype "input"))
      (node (ref "C9") (pin "2") (pinfunction "2_2") (pintype "input"))
      (node (ref "R9") (pin "2") (pinfunction "2_2") (pintype "input"))
      (node (ref "U6") (pin "1") (pinfunction "1_1") (pintype "unspecified"))
      (node (ref "U9") (pin "5") (pinfunction "VOUT_5") (pintype "input"))
    )
    (net (code "54") (name "/VCCOP") (class "Default")
      (node (ref "C13") (pin "2") (pinfunction "2_2") (pintype "input"))
      (node (ref "C14") (pin "1") (pinfunction "1_1") (pintype "input"))
      (node (ref "H10") (pin "5") (pinfunction "5_5") (pintype "input"))
      (node (ref "R11") (pin "2") (pinfunction "2_2") (pintype "input"))
      (node (ref "U10") (pin "5") (pinfunction "VOUT_5") (pintype "input"))
    )
    (net (code "55") (name "/VCCSERVO") (class "Default")
      (node (ref "C1") (pin "2") (pinfunction "2_2") (pintype "input"))
      (node (ref "C2") (pin "2") (pinfunction "2_2") (pintype "input"))
      (node (ref "H11") (pin "2") (pinfunction "2_2") (pintype "input"))
      (node (ref "L1") (pin "2") (pinfunction "2_2") (pintype "input"))
      (node (ref "R1") (pin "2") (pinfunction "2_2") (pintype "input"))
      (node (ref "R2") (pin "2") (pinfunction "2_2") (pintype "input"))
    )
    (net (code "56") (name "/VIN") (class "Default")
      (node (ref "C3") (pin "1") (pinfunction "1_1") (pintype "input"))
      (node (ref "C4") (pin "2") (pinfunction "2_2") (pintype "input"))
      (node (ref "C5") (pin "2") (pinfunction "2_2") (pintype "input"))
      (node (ref "C6") (pin "1") (pinfunction "1_1") (pintype "input"))
      (node (ref "R4") (pin "1") (pinfunction "1_1") (pintype "input"))
      (node (ref "R5") (pin "1") (pinfunction "1_1") (pintype "input"))
      (node (ref "SW1") (pin "2") (pinfunction "2_2") (pintype "unspecified"))
      (node (ref "U7") (pin "4") (pinfunction "IN_4") (pintype "input"))
      (node (ref "U8") (pin "1") (pinfunction "INPUT_1") (pintype "input"))
    )
    (net (code "57") (name "GND5V") (class "Default")
      (node (ref "C11") (pin "2") (pinfunction "2_2") (pintype "input"))
      (node (ref "C12") (pin "1") (pinfunction "1_1") (pintype "input"))
      (node (ref "C15") (pin "2") (pinfunction "2_2") (pintype "input"))
      (node (ref "C16") (pin "1") (pinfunction "1_1") (pintype "input"))
      (node (ref "C17") (pin "1") (pinfunction "1_1") (pintype "input"))
      (node (ref "C18") (pin "2") (pinfunction "2_2") (pintype "input"))
      (node (ref "C19") (pin "2") (pinfunction "2_2") (pintype "input"))
      (node (ref "C20") (pin "1") (pinfunction "1_1") (pintype "input"))
      (node (ref "C21") (pin "2") (pinfunction "2_2") (pintype "input"))
      (node (ref "C22") (pin "2") (pinfunction "2_2") (pintype "input"))
      (node (ref "C23") (pin "2") (pinfunction "2_2") (pintype "input"))
      (node (ref "C24") (pin "2") (pinfunction "2_2") (pintype "input"))
      (node (ref "C7") (pin "1") (pinfunction "1_1") (pintype "input"))
      (node (ref "C8") (pin "2") (pinfunction "2_2") (pintype "input"))
      (node (ref "H1") (pin "6") (pinfunction "6_6") (pintype "input"))
      (node (ref "H2") (pin "6") (pinfunction "6_6") (pintype "input"))
      (node (ref "H4") (pin "2") (pinfunction "2_2") (pintype "input"))
      (node (ref "H5") (pin "2") (pinfunction "2_2") (pintype "input"))
      (node (ref "H6") (pin "1") (pinfunction "1_1") (pintype "input"))
      (node (ref "H7") (pin "2") (pinfunction "2_2") (pintype "input"))
      (node (ref "H8") (pin "2") (pinfunction "2_2") (pintype "input"))
      (node (ref "LED2") (pin "1") (pinfunction "C_1") (pintype "input"))
      (node (ref "LED5") (pin "1") (pinfunction "C_1") (pintype "input"))
      (node (ref "Q1") (pin "2") (pinfunction "E_2") (pintype "input"))
      (node (ref "R10") (pin "1") (pinfunction "1_1") (pintype "input"))
      (node (ref "R12") (pin "1") (pinfunction "1_1") (pintype "input"))
      (node (ref "R8") (pin "2") (pinfunction "2_2") (pintype "input"))
      (node (ref "SW4") (pin "2") (pinfunction "2_2") (pintype "input"))
      (node (ref "SW5") (pin "2") (pinfunction "2_2") (pintype "input"))
      (node (ref "SW6") (pin "2") (pinfunction "2_2") (pintype "input"))
      (node (ref "SW7") (pin "2") (pinfunction "2_2") (pintype "input"))
      (node (ref "U10") (pin "2") (pinfunction "GND_2") (pintype "input"))
      (node (ref "U11") (pin "2") (pinfunction "GND_2") (pintype "input"))
      (node (ref "U5") (pin "1") (pinfunction "GND_1") (pintype "input"))
      (node (ref "U5") (pin "3") (pinfunction "GND_3") (pintype "input"))
      (node (ref "U9") (pin "2") (pinfunction "GND_2") (pintype "input"))
    )
    (net (code "58") (name "GNDCAM") (class "Default")
      (node (ref "C10") (pin "2") (pinfunction "2_2") (pintype "input"))
      (node (ref "C9") (pin "1") (pinfunction "1_1") (pintype "input"))
      (node (ref "LED3") (pin "1") (pinfunction "C_1") (pintype "input"))
      (node (ref "R10") (pin "2") (pinfunction "2_2") (pintype "input"))
      (node (ref "U6") (pin "13") (pinfunction "13_13") (pintype "unspecified"))
      (node (ref "U6") (pin "3") (pinfunction "3_3") (pintype "unspecified"))
    )
    (net (code "59") (name "GNDOP") (class "Default")
      (node (ref "C13") (pin "1") (pinfunction "1_1") (pintype "input"))
      (node (ref "C14") (pin "2") (pinfunction "2_2") (pintype "input"))
      (node (ref "H10") (pin "6") (pinfunction "6_6") (pintype "input"))
      (node (ref "LED4") (pin "1") (pinfunction "C_1") (pintype "input"))
      (node (ref "R12") (pin "2") (pinfunction "2_2") (pintype "input"))
    )
    (net (code "60") (name "GNDSERVO") (class "Default")
      (node (ref "C1") (pin "1") (pinfunction "1_1") (pintype "input"))
      (node (ref "C2") (pin "1") (pinfunction "1_1") (pintype "input"))
      (node (ref "H11") (pin "3") (pinfunction "3_3") (pintype "input"))
      (node (ref "LED1") (pin "1") (pinfunction "C_1") (pintype "input"))
      (node (ref "R6") (pin "2") (pinfunction "2_2") (pintype "input"))
    )
    (net (code "61") (name "GNDVIN") (class "Default")
      (node (ref "C3") (pin "2") (pinfunction "2_2") (pintype "input"))
      (node (ref "C4") (pin "1") (pinfunction "1_1") (pintype "input"))
      (node (ref "C5") (pin "1") (pinfunction "1_1") (pintype "input"))
      (node (ref "C6") (pin "2") (pinfunction "2_2") (pintype "input"))
      (node (ref "CN4") (pin "1") (pinfunction "1_1") (pintype "input"))
      (node (ref "D1") (pin "1") (pinfunction "A_1") (pintype "unspecified"))
      (node (ref "H9") (pin "1") (pinfunction "1_1") (pintype "input"))
      (node (ref "H9") (pin "6") (pinfunction "6_6") (pintype "input"))
      (node (ref "P1") (pin "2") (pinfunction "2_2") (pintype "input"))
      (node (ref "R3") (pin "3") (pinfunction "3_3") (pintype "input"))
      (node (ref "R6") (pin "1") (pinfunction "1_1") (pintype "input"))
      (node (ref "R8") (pin "1") (pinfunction "1_1") (pintype "input"))
      (node (ref "U7") (pin "7") (pinfunction "GND_7") (pintype "input"))
      (node (ref "U7") (pin "8") (pinfunction "GND_8") (pintype "input"))
      (node (ref "U8") (pin "2") (pinfunction "GND_2") (pintype "input"))
      (node (ref "U8") (pin "4") (pinfunction "GND_4") (pintype "input"))
    )
    (net (code "62") (name "Net-(CN4-Pad2)") (class "Default")
      (node (ref "CN4") (pin "2") (pinfunction "2_2") (pintype "input"))
      (node (ref "SW1") (pin "1") (pinfunction "1_1") (pintype "unspecified"))
      (node (ref "SW2") (pin "2") (pinfunction "2_2") (pintype "unspecified"))
    )
    (net (code "63") (name "Net-(D1-K)") (class "Default")
      (node (ref "D1") (pin "2") (pinfunction "K_2") (pintype "unspecified"))
      (node (ref "L1") (pin "1") (pinfunction "1_1") (pintype "input"))
      (node (ref "U7") (pin "5") (pinfunction "SW_5") (pintype "input"))
      (node (ref "U7") (pin "6") (pinfunction "SW_6") (pintype "input"))
    )
    (net (code "64") (name "Net-(LED1-A)") (class "Default")
      (node (ref "LED1") (pin "2") (pinfunction "A_2") (pintype "input"))
      (node (ref "R1") (pin "1") (pinfunction "1_1") (pintype "input"))
    )
    (net (code "65") (name "Net-(LED2-A)") (class "Default")
      (node (ref "LED2") (pin "2") (pinfunction "A_2") (pintype "input"))
      (node (ref "R7") (pin "1") (pinfunction "1_1") (pintype "input"))
    )
    (net (code "66") (name "Net-(LED3-A)") (class "Default")
      (node (ref "LED3") (pin "2") (pinfunction "A_2") (pintype "input"))
      (node (ref "R9") (pin "1") (pinfunction "1_1") (pintype "input"))
    )
    (net (code "67") (name "Net-(LED4-A)") (class "Default")
      (node (ref "LED4") (pin "2") (pinfunction "A_2") (pintype "input"))
      (node (ref "R11") (pin "1") (pinfunction "1_1") (pintype "input"))
    )
    (net (code "68") (name "Net-(LED5-A)") (class "Default")
      (node (ref "LED5") (pin "2") (pinfunction "A_2") (pintype "input"))
      (node (ref "R13") (pin "1") (pinfunction "1_1") (pintype "input"))
    )
    (net (code "69") (name "Net-(LED6-A)") (class "Default")
      (node (ref "LED6") (pin "2") (pinfunction "A_2") (pintype "input"))
      (node (ref "R16") (pin "2") (pinfunction "2_2") (pintype "input"))
    )
    (net (code "70") (name "Net-(LED7-A)") (class "Default")
      (node (ref "LED7") (pin "2") (pinfunction "A_2") (pintype "input"))
      (node (ref "R17") (pin "2") (pinfunction "2_2") (pintype "input"))
    )
    (net (code "71") (name "Net-(LED8-A)") (class "Default")
      (node (ref "LED8") (pin "2") (pinfunction "A_2") (pintype "input"))
      (node (ref "R18") (pin "2") (pinfunction "2_2") (pintype "input"))
    )
    (net (code "72") (name "Net-(P1-Pad1)") (class "Default")
      (node (ref "P1") (pin "1") (pinfunction "1_1") (pintype "input"))
      (node (ref "SW2") (pin "1") (pinfunction "1_1") (pintype "unspecified"))
    )
    (net (code "73") (name "Net-(Q1-B)") (class "Default")
      (node (ref "Q1") (pin "1") (pinfunction "B_1") (pintype "input"))
      (node (ref "R15") (pin "1") (pinfunction "1_1") (pintype "input"))
    )
    (net (code "74") (name "Net-(Q1-C)") (class "Default")
      (node (ref "BUZZER1") (pin "2") (pinfunction "2_2") (pintype "input"))
      (node (ref "Q1") (pin "3") (pinfunction "C_3") (pintype "input"))
    )
    (net (code "75") (name "Net-(U7-EN)") (class "Default")
      (node (ref "R4") (pin "2") (pinfunction "2_2") (pintype "input"))
      (node (ref "U7") (pin "2") (pinfunction "EN_2") (pintype "input"))
    )
    (net (code "76") (name "Net-(U7-FB)") (class "Default")
      (node (ref "R2") (pin "1") (pinfunction "1_1") (pintype "input"))
      (node (ref "R3") (pin "2") (pinfunction "2_2") (pintype "input"))
      (node (ref "U7") (pin "1") (pinfunction "FB_1") (pintype "input"))
    )
    (net (code "77") (name "Net-(U7-OSCET)") (class "Default")
      (node (ref "R5") (pin "2") (pinfunction "2_2") (pintype "input"))
      (node (ref "U7") (pin "3") (pinfunction "OSCET_3") (pintype "input"))
    )
    (net (code "78") (name "unconnected-(H1-Pad1)") (class "Default")
      (node (ref "H1") (pin "1") (pinfunction "1_1") (pintype "input+no_connect"))
    )
    (net (code "79") (name "unconnected-(H1-Pad2)") (class "Default")
      (node (ref "H1") (pin "2") (pinfunction "2_2") (pintype "input+no_connect"))
    )
    (net (code "80") (name "unconnected-(H2-Pad1)") (class "Default")
      (node (ref "H2") (pin "1") (pinfunction "1_1") (pintype "input+no_connect"))
    )
    (net (code "81") (name "unconnected-(H2-Pad2)") (class "Default")
      (node (ref "H2") (pin "2") (pinfunction "2_2") (pintype "input+no_connect"))
    )
    (net (code "82") (name "unconnected-(H4-Pad7)") (class "Default")
      (node (ref "H4") (pin "7") (pinfunction "7_7") (pintype "input+no_connect"))
    )
    (net (code "83") (name "unconnected-(H4-Pad8)") (class "Default")
      (node (ref "H4") (pin "8") (pinfunction "8_8") (pintype "input+no_connect"))
    )
    (net (code "84") (name "unconnected-(R3-Pad1)") (class "Default")
      (node (ref "R3") (pin "1") (pinfunction "1_1") (pintype "input+no_connect"))
    )
    (net (code "85") (name "unconnected-(SW1-Pad3)") (class "Default")
      (node (ref "SW1") (pin "3") (pinfunction "3_3") (pintype "unspecified+no_connect"))
    )
    (net (code "86") (name "unconnected-(SW2-Pad3)") (class "Default")
      (node (ref "SW2") (pin "3") (pinfunction "3_3") (pintype "unspecified+no_connect"))
    )
    (net (code "87") (name "unconnected-(U5-00.8-Pad107)") (class "Default")
      (node (ref "U5") (pin "107") (pinfunction "00.8_107") (pintype "input+no_connect"))
    )
    (net (code "88") (name "unconnected-(U5-00.9-Pad108)") (class "Default")
      (node (ref "U5") (pin "108") (pinfunction "00.9_108") (pintype "input+no_connect"))
    )
    (net (code "89") (name "unconnected-(U5-00.12-Pad109)") (class "Default")
      (node (ref "U5") (pin "109") (pinfunction "00.12_109") (pintype "input+no_connect"))
    )
    (net (code "90") (name "unconnected-(U5-02.8-Pad98)") (class "Default")
      (node (ref "U5") (pin "98") (pinfunction "02.8_98") (pintype "input+no_connect"))
    )
    (net (code "91") (name "unconnected-(U5-10.2-Pad86)") (class "Default")
      (node (ref "U5") (pin "86") (pinfunction "10.2_86") (pintype "input+no_connect"))
    )
    (net (code "92") (name "unconnected-(U5-11.2-Pad78)") (class "Default")
      (node (ref "U5") (pin "78") (pinfunction "11.2_78") (pintype "input+no_connect"))
    )
    (net (code "93") (name "unconnected-(U5-11.3-Pad79)") (class "Default")
      (node (ref "U5") (pin "79") (pinfunction "11.3_79") (pintype "input+no_connect"))
    )
    (net (code "94") (name "unconnected-(U5-11.6-Pad80)") (class "Default")
      (node (ref "U5") (pin "80") (pinfunction "11.6_80") (pintype "input+no_connect"))
    )
    (net (code "95") (name "unconnected-(U5-11.9-Pad81)") (class "Default")
      (node (ref "U5") (pin "81") (pinfunction "11.9_81") (pintype "input+no_connect"))
    )
    (net (code "96") (name "unconnected-(U5-11.10-Pad82)") (class "Default")
      (node (ref "U5") (pin "82") (pinfunction "11.10_82") (pintype "input+no_connect"))
    )
    (net (code "97") (name "unconnected-(U5-11.11-Pad83)") (class "Default")
      (node (ref "U5") (pin "83") (pinfunction "11.11_83") (pintype "input+no_connect"))
    )
    (net (code "98") (name "unconnected-(U5-11.12-Pad84)") (class "Default")
      (node (ref "U5") (pin "84") (pinfunction "11.12_84") (pintype "input+no_connect"))
    )
    (net (code "99") (name "unconnected-(U5-13.0-Pad74)") (class "Default")
      (node (ref "U5") (pin "74") (pinfunction "13.0_74") (pintype "input+no_connect"))
    )
    (net (code "100") (name "unconnected-(U5-13.1-Pad75)") (class "Default")
      (node (ref "U5") (pin "75") (pinfunction "13.1_75") (pintype "input+no_connect"))
    )
    (net (code "101") (name "unconnected-(U5-13.2-Pad76)") (class "Default")
      (node (ref "U5") (pin "76") (pinfunction "13.2_76") (pintype "input+no_connect"))
    )
    (net (code "102") (name "unconnected-(U5-13.3-Pad77)") (class "Default")
      (node (ref "U5") (pin "77") (pinfunction "13.3_77") (pintype "input+no_connect"))
    )
    (net (code "103") (name "unconnected-(U5-14.2-Pad69)") (class "Default")
      (node (ref "U5") (pin "69") (pinfunction "14.2_69") (pintype "input+no_connect"))
    )
    (net (code "104") (name "unconnected-(U5-14.3-Pad70)") (class "Default")
      (node (ref "U5") (pin "70") (pinfunction "14.3_70") (pintype "input+no_connect"))
    )
    (net (code "105") (name "unconnected-(U5-14.4-Pad71)") (class "Default")
      (node (ref "U5") (pin "71") (pinfunction "14.4_71") (pintype "input+no_connect"))
    )
    (net (code "106") (name "unconnected-(U5-14.5-Pad72)") (class "Default")
      (node (ref "U5") (pin "72") (pinfunction "14.5_72") (pintype "input+no_connect"))
    )
    (net (code "107") (name "unconnected-(U5-14.6-Pad73)") (class "Default")
      (node (ref "U5") (pin "73") (pinfunction "14.6_73") (pintype "input+no_connect"))
    )
    (net (code "108") (name "unconnected-(U5-15.6-Pad64)") (class "Default")
      (node (ref "U5") (pin "64") (pinfunction "15.6_64") (pintype "input+no_connect"))
    )
    (net (code "109") (name "unconnected-(U5-15.7-Pad65)") (class "Default")
      (node (ref "U5") (pin "65") (pinfunction "15.7_65") (pintype "input+no_connect"))
    )
    (net (code "110") (name "unconnected-(U5-15.8-Pad66)") (class "Default")
      (node (ref "U5") (pin "66") (pinfunction "15.8_66") (pintype "input+no_connect"))
    )
    (net (code "111") (name "unconnected-(U5-20.0-Pad44)") (class "Default")
      (node (ref "U5") (pin "44") (pinfunction "20.0_44") (pintype "input+no_connect"))
    )
    (net (code "112") (name "unconnected-(U5-20.2-Pad45)") (class "Default")
      (node (ref "U5") (pin "45") (pinfunction "20.2_45") (pintype "input+no_connect"))
    )
    (net (code "113") (name "unconnected-(U5-20.3-Pad46)") (class "Default")
      (node (ref "U5") (pin "46") (pinfunction "20.3_46") (pintype "input+no_connect"))
    )
    (net (code "114") (name "unconnected-(U5-20.6-Pad49)") (class "Default")
      (node (ref "U5") (pin "49") (pinfunction "20.6_49") (pintype "input+no_connect"))
    )
    (net (code "115") (name "unconnected-(U5-20.7-Pad50)") (class "Default")
      (node (ref "U5") (pin "50") (pinfunction "20.7_50") (pintype "input+no_connect"))
    )
    (net (code "116") (name "unconnected-(U5-20.8-Pad51)") (class "Default")
      (node (ref "U5") (pin "51") (pinfunction "20.8_51") (pintype "input+no_connect"))
    )
    (net (code "117") (name "unconnected-(U5-20.9-Pad52)") (class "Default")
      (node (ref "U5") (pin "52") (pinfunction "20.9_52") (pintype "input+no_connect"))
    )
    (net (code "118") (name "unconnected-(U5-21.3-Pad39)") (class "Default")
      (node (ref "U5") (pin "39") (pinfunction "21.3_39") (pintype "input+no_connect"))
    )
    (net (code "119") (name "unconnected-(U5-21.5-Pad41)") (class "Default")
      (node (ref "U5") (pin "41") (pinfunction "21.5_41") (pintype "input+no_connect"))
    )
    (net (code "120") (name "unconnected-(U5-21.6-Pad42)") (class "Default")
      (node (ref "U5") (pin "42") (pinfunction "21.6_42") (pintype "input+no_connect"))
    )
    (net (code "121") (name "unconnected-(U5-21.7-Pad43)") (class "Default")
      (node (ref "U5") (pin "43") (pinfunction "21.7_43") (pintype "input+no_connect"))
    )
    (net (code "122") (name "unconnected-(U5-22.0-Pad34)") (class "Default")
      (node (ref "U5") (pin "34") (pinfunction "22.0_34") (pintype "input+no_connect"))
    )
    (net (code "123") (name "unconnected-(U5-22.1-Pad35)") (class "Default")
      (node (ref "U5") (pin "35") (pinfunction "22.1_35") (pintype "input+no_connect"))
    )
    (net (code "124") (name "unconnected-(U5-23.1-Pad33)") (class "Default")
      (node (ref "U5") (pin "33") (pinfunction "23.1_33") (pintype "input+no_connect"))
    )
    (net (code "125") (name "unconnected-(U5-32.4-Pad32)") (class "Default")
      (node (ref "U5") (pin "32") (pinfunction "32.4_32") (pintype "input+no_connect"))
    )
    (net (code "126") (name "unconnected-(U5-33.8-Pad26)") (class "Default")
      (node (ref "U5") (pin "26") (pinfunction "33.8_26") (pintype "input+no_connect"))
    )
    (net (code "127") (name "unconnected-(U5-A4-Pad17)") (class "Default")
      (node (ref "U5") (pin "17") (pinfunction "A4_17") (pintype "input+no_connect"))
    )
    (net (code "128") (name "unconnected-(U5-A5-Pad16)") (class "Default")
      (node (ref "U5") (pin "16") (pinfunction "A5_16") (pintype "input+no_connect"))
    )
    (net (code "129") (name "unconnected-(U5-A6-Pad15)") (class "Default")
      (node (ref "U5") (pin "15") (pinfunction "A6_15") (pintype "input+no_connect"))
    )
    (net (code "130") (name "unconnected-(U5-A7-Pad14)") (class "Default")
      (node (ref "U5") (pin "14") (pinfunction "A7_14") (pintype "input+no_connect"))
    )
    (net (code "131") (name "unconnected-(U5-A8-Pad13)") (class "Default")
      (node (ref "U5") (pin "13") (pinfunction "A8_13") (pintype "input+no_connect"))
    )
    (net (code "132") (name "unconnected-(U5-A10-Pad12)") (class "Default")
      (node (ref "U5") (pin "12") (pinfunction "A10_12") (pintype "input+no_connect"))
    )
    (net (code "133") (name "unconnected-(U5-A11-Pad11)") (class "Default")
      (node (ref "U5") (pin "11") (pinfunction "A11_11") (pintype "input+no_connect"))
    )
    (net (code "134") (name "unconnected-(U5-A12-Pad10)") (class "Default")
      (node (ref "U5") (pin "10") (pinfunction "A12_10") (pintype "input+no_connect"))
    )
    (net (code "135") (name "unconnected-(U5-A13-Pad9)") (class "Default")
      (node (ref "U5") (pin "9") (pinfunction "A13_9") (pintype "input+no_connect"))
    )
    (net (code "136") (name "unconnected-(U5-A16-Pad8)") (class "Default")
      (node (ref "U5") (pin "8") (pinfunction "A16_8") (pintype "input+no_connect"))
    )
    (net (code "137") (name "unconnected-(U5-A17-Pad7)") (class "Default")
      (node (ref "U5") (pin "7") (pinfunction "A17_7") (pintype "input+no_connect"))
    )
    (net (code "138") (name "unconnected-(U5-A20-Pad6)") (class "Default")
      (node (ref "U5") (pin "6") (pinfunction "A20_6") (pintype "input+no_connect"))
    )
    (net (code "139") (name "unconnected-(U5-A21-Pad5)") (class "Default")
      (node (ref "U5") (pin "5") (pinfunction "A21_5") (pintype "input+no_connect"))
    )
    (net (code "140") (name "unconnected-(U5-A24-Pad122)") (class "Default")
      (node (ref "U5") (pin "122") (pinfunction "A24_122") (pintype "input+no_connect"))
    )
    (net (code "141") (name "unconnected-(U5-A25-Pad121)") (class "Default")
      (node (ref "U5") (pin "121") (pinfunction "A25_121") (pintype "input+no_connect"))
    )
    (net (code "142") (name "unconnected-(U5-A35-Pad120)") (class "Default")
      (node (ref "U5") (pin "120") (pinfunction "A35_120") (pintype "input+no_connect"))
    )
    (net (code "143") (name "unconnected-(U5-A36-Pad119)") (class "Default")
      (node (ref "U5") (pin "119") (pinfunction "A36_119") (pintype "input+no_connect"))
    )
    (net (code "144") (name "unconnected-(U5-A37-Pad118)") (class "Default")
      (node (ref "U5") (pin "118") (pinfunction "A37_118") (pintype "input+no_connect"))
    )
    (net (code "145") (name "unconnected-(U5-A38-Pad117)") (class "Default")
      (node (ref "U5") (pin "117") (pinfunction "A38_117") (pintype "input+no_connect"))
    )
    (net (code "146") (name "unconnected-(U5-A39-Pad116)") (class "Default")
      (node (ref "U5") (pin "116") (pinfunction "A39_116") (pintype "input+no_connect"))
    )
    (net (code "147") (name "unconnected-(U5-A44-Pad115)") (class "Default")
      (node (ref "U5") (pin "115") (pinfunction "A44_115") (pintype "input+no_connect"))
    )
    (net (code "148") (name "unconnected-(U5-A45-Pad114)") (class "Default")
      (node (ref "U5") (pin "114") (pinfunction "A45_114") (pintype "input+no_connect"))
    )
    (net (code "149") (name "unconnected-(U5-A46-Pad113)") (class "Default")
      (node (ref "U5") (pin "113") (pinfunction "A46_113") (pintype "input+no_connect"))
    )
    (net (code "150") (name "unconnected-(U5-A47-Pad112)") (class "Default")
      (node (ref "U5") (pin "112") (pinfunction "A47_112") (pintype "input+no_connect"))
    )
    (net (code "151") (name "unconnected-(U5-A48-Pad111)") (class "Default")
      (node (ref "U5") (pin "111") (pinfunction "A48_111") (pintype "input+no_connect"))
    )
    (net (code "152") (name "unconnected-(U5-A49-Pad110)") (class "Default")
      (node (ref "U5") (pin "110") (pinfunction "A49_110") (pintype "input+no_connect"))
    )
    (net (code "153") (name "unconnected-(U5-ESR0-Pad48)") (class "Default")
      (node (ref "U5") (pin "48") (pinfunction "ESR0_48") (pintype "input+no_connect"))
    )
    (net (code "154") (name "unconnected-(U5-ESR1-Pad47)") (class "Default")
      (node (ref "U5") (pin "47") (pinfunction "ESR1_47") (pintype "input+no_connect"))
    )
    (net (code "155") (name "unconnected-(U6-Pad7)") (class "Default")
      (node (ref "U6") (pin "7") (pinfunction "7_7") (pintype "unspecified+no_connect"))
    )
    (net (code "156") (name "unconnected-(U9-NC-Pad4)") (class "Default")
      (node (ref "U9") (pin "4") (pinfunction "NC_4") (pintype "input+no_connect"))
    )
    (net (code "157") (name "unconnected-(U10-NC-Pad4)") (class "Default")
      (node (ref "U10") (pin "4") (pinfunction "NC_4") (pintype "input+no_connect"))
    )
    (net (code "158") (name "unconnected-(U11-NC-Pad4)") (class "Default")
      (node (ref "U11") (pin "4") (pinfunction "NC_4") (pintype "input+no_connect"))
    )
  )
)
